# uC_input.net
KiCad netlist of a schematic drawn in Altium Designer
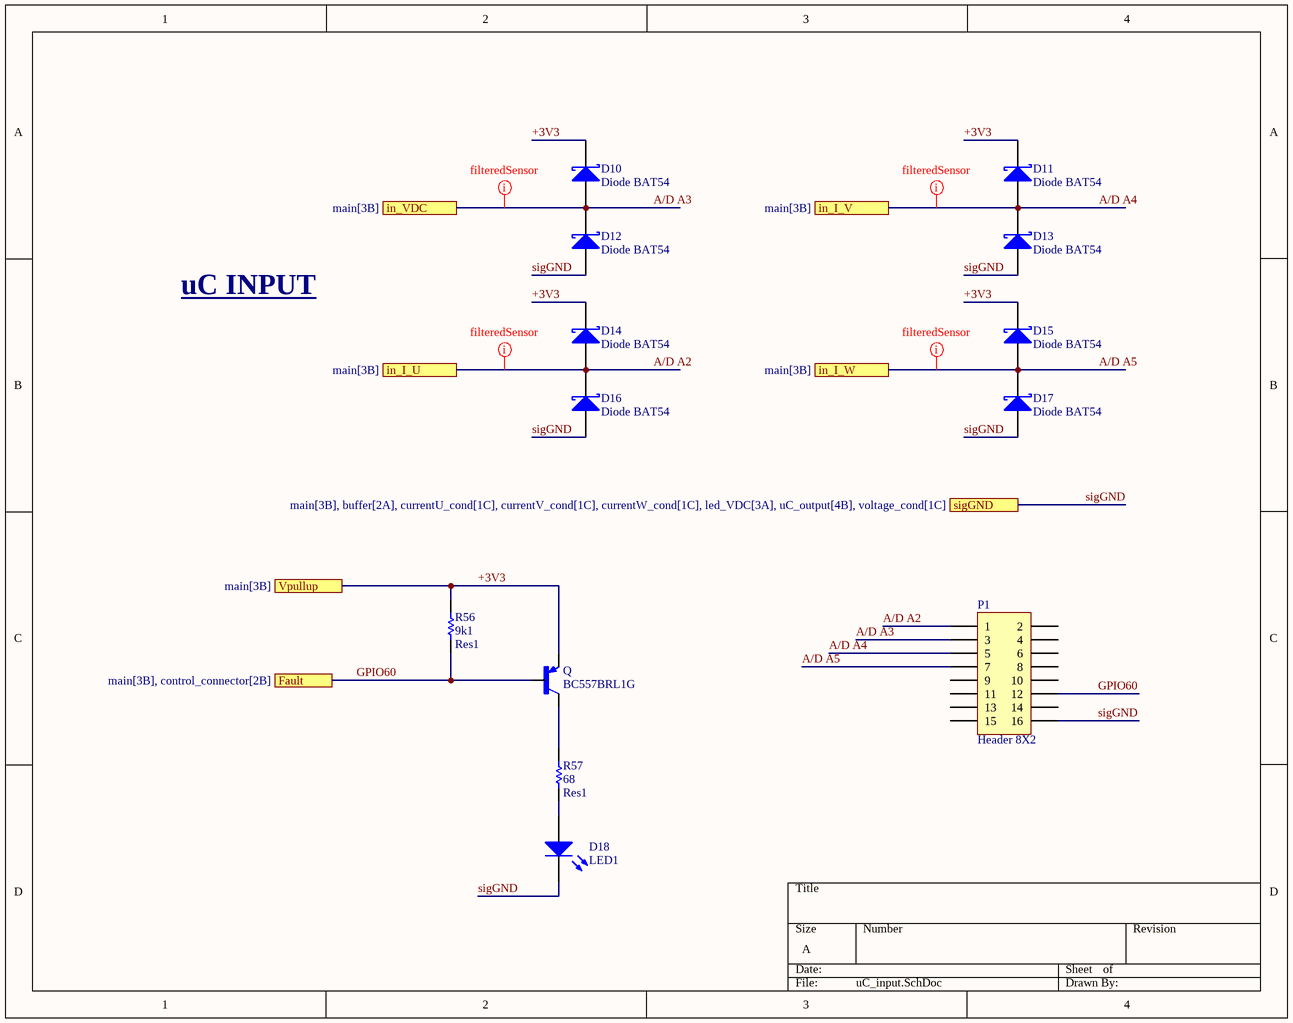
[diagram p0: uC_input.SchDoc]

(export (version "E")
  (design (tool "Eeschema 10.0.6"))
  (components
    (comp (ref "D10")
      (value "Diode BAT54")
      (footprint "DO-41_mod")
      (description "Schottky Rectifier")
      (fields (field (name "PUBLISHER") "Altium Limited"))
      (libsource (lib "LABSTEPS_Project") (part "Diode 11DQ03"))
    )
    (comp (ref "D11")
      (value "Diode BAT54")
      (footprint "DO-41_mod")
      (description "Schottky Rectifier")
      (fields (field (name "PUBLISHER") "Altium Limited"))
      (libsource (lib "LABSTEPS_Project") (part "Diode 11DQ03"))
    )
    (comp (ref "D12")
      (value "Diode BAT54")
      (footprint "DO-41_mod")
      (description "Schottky Rectifier")
      (fields (field (name "PUBLISHER") "Altium Limited"))
      (libsource (lib "LABSTEPS_Project") (part "Diode 11DQ03"))
    )
    (comp (ref "D13")
      (value "Diode BAT54")
      (footprint "DO-41_mod")
      (description "Schottky Rectifier")
      (fields (field (name "PUBLISHER") "Altium Limited"))
      (libsource (lib "LABSTEPS_Project") (part "Diode 11DQ03"))
    )
    (comp (ref "D14")
      (value "Diode BAT54")
      (footprint "DO-41_mod")
      (description "Schottky Rectifier")
      (fields (field (name "PUBLISHER") "Altium Limited"))
      (libsource (lib "LABSTEPS_Project") (part "Diode 11DQ03"))
    )
    (comp (ref "D15")
      (value "Diode BAT54")
      (footprint "DO-41_mod")
      (description "Schottky Rectifier")
      (fields (field (name "PUBLISHER") "Altium Limited"))
      (libsource (lib "LABSTEPS_Project") (part "Diode 11DQ03"))
    )
    (comp (ref "D16")
      (value "Diode BAT54")
      (footprint "DO-41_mod")
      (description "Schottky Rectifier")
      (fields (field (name "PUBLISHER") "Altium Limited"))
      (libsource (lib "LABSTEPS_Project") (part "Diode 11DQ03"))
    )
    (comp (ref "D17")
      (value "Diode BAT54")
      (footprint "DO-41_mod")
      (description "Schottky Rectifier")
      (fields (field (name "PUBLISHER") "Altium Limited"))
      (libsource (lib "LABSTEPS_Project") (part "Diode 11DQ03"))
    )
    (comp (ref "D18")
      (value "LED1")
      (footprint "PIN2_mod")
      (description "Typical RED GaAs LED")
      (fields (field (name "PUBLISHER") "Altium Limited"))
      (libsource (lib "moded_symbol") (part "LED1"))
    )
    (comp (ref "P1")
      (value "Header 8X2")
      (footprint "HDR2X8_mod")
      (description "Header, 8-Pin, Dual row")
      (fields (field (name "PUBLISHER") "Altium Limited"))
      (libsource (lib "LABSTEPS_Project") (part "Header 8X2"))
    )
    (comp (ref "Q")
      (value "BC557BRL1G")
      (footprint "TO92260P520H933-3_mod")
      (description "Bipolar (BJT) Transistor PNP 45V 100mA 320MHz 625mW Through Hole TO-92-3")
      (fields
        (field (name "MF") "ON Semiconductor")
        (field (name "BUYPART") "https://www.snapeda.com/parts/BC557BRL1G/ON%20Semiconductor/view-part/3219064/?ref=eda")
      )
      (libsource (lib "BC557") (part "BC557BRL1G"))
    )
    (comp (ref "R56")
      (value "Res1")
      (footprint "AXIAL-0.3_mod")
      (description "Resistor")
      (fields (field (name "ALTIUM_VALUE") "9k1") (field (name "PUBLISHER") "Altium Limited"))
      (libsource (lib "LABSTEPS_Project") (part "Res1"))
    )
    (comp (ref "R57")
      (value "Res1")
      (footprint "AXIAL-0.3_mod")
      (description "Resistor")
      (fields (field (name "ALTIUM_VALUE") "68") (field (name "PUBLISHER") "Altium Limited"))
      (libsource (lib "LABSTEPS_Project") (part "Res1"))
    )
  )
  (nets
    (net (code "1") (name "/+3V3") (class "Default")
      (node (ref "D10") (pin "2") (pinfunction "K_2") (pintype "passive"))
      (node (ref "D11") (pin "2") (pinfunction "K_2") (pintype "passive"))
      (node (ref "D14") (pin "2") (pinfunction "K_2") (pintype "passive"))
      (node (ref "D15") (pin "2") (pinfunction "K_2") (pintype "passive"))
      (node (ref "Q") (pin "3") (pinfunction "E_3") (pintype "passive"))
      (node (ref "R56") (pin "1") (pinfunction "1_1") (pintype "passive"))
    )
    (net (code "2") (name "/A{slash}D A2") (class "Default")
      (node (ref "D14") (pin "1") (pinfunction "A_1") (pintype "passive"))
      (node (ref "D16") (pin "2") (pinfunction "K_2") (pintype "passive"))
      (node (ref "P1") (pin "1") (pinfunction "1_1") (pintype "passive"))
    )
    (net (code "3") (name "/A{slash}D A3") (class "Default")
      (node (ref "D10") (pin "1") (pinfunction "A_1") (pintype "passive"))
      (node (ref "D12") (pin "2") (pinfunction "K_2") (pintype "passive"))
      (node (ref "P1") (pin "3") (pinfunction "3_3") (pintype "passive"))
    )
    (net (code "4") (name "/A{slash}D A4") (class "Default")
      (node (ref "D11") (pin "1") (pinfunction "A_1") (pintype "passive"))
      (node (ref "D13") (pin "2") (pinfunction "K_2") (pintype "passive"))
      (node (ref "P1") (pin "5") (pinfunction "5_5") (pintype "passive"))
    )
    (net (code "5") (name "/A{slash}D A5") (class "Default")
      (node (ref "D15") (pin "1") (pinfunction "A_1") (pintype "passive"))
      (node (ref "D17") (pin "2") (pinfunction "K_2") (pintype "passive"))
      (node (ref "P1") (pin "7") (pinfunction "7_7") (pintype "passive"))
    )
    (net (code "6") (name "/GPIO60") (class "Default")
      (node (ref "P1") (pin "12") (pinfunction "12_12") (pintype "passive"))
      (node (ref "Q") (pin "2") (pinfunction "B_2") (pintype "passive"))
      (node (ref "R56") (pin "2") (pinfunction "2_2") (pintype "passive"))
    )
    (net (code "7") (name "/sigGND") (class "Default")
      (node (ref "D12") (pin "1") (pinfunction "A_1") (pintype "passive"))
      (node (ref "D13") (pin "1") (pinfunction "A_1") (pintype "passive"))
      (node (ref "D16") (pin "1") (pinfunction "A_1") (pintype "passive"))
      (node (ref "D17") (pin "1") (pinfunction "A_1") (pintype "passive"))
      (node (ref "D18") (pin "2") (pinfunction "K_2") (pintype "passive"))
      (node (ref "P1") (pin "16") (pinfunction "16_16") (pintype "passive"))
    )
    (net (code "8") (name "Net-(D18-A)") (class "Default")
      (node (ref "D18") (pin "1") (pinfunction "A_1") (pintype "passive"))
      (node (ref "R57") (pin "2") (pinfunction "2_2") (pintype "passive"))
    )
    (net (code "9") (name "Net-(Q-C)") (class "Default")
      (node (ref "Q") (pin "1") (pinfunction "C_1") (pintype "passive"))
      (node (ref "R57") (pin "1") (pinfunction "1_1") (pintype "passive"))
    )
    (net (code "10") (name "unconnected-(P1-Pad2)") (class "Default")
      (node (ref "P1") (pin "2") (pinfunction "2_2") (pintype "passive"))
    )
    (net (code "11") (name "unconnected-(P1-Pad4)") (class "Default")
      (node (ref "P1") (pin "4") (pinfunction "4_4") (pintype "passive"))
    )
    (net (code "12") (name "unconnected-(P1-Pad6)") (class "Default")
      (node (ref "P1") (pin "6") (pinfunction "6_6") (pintype "passive"))
    )
    (net (code "13") (name "unconnected-(P1-Pad8)") (class "Default")
      (node (ref "P1") (pin "8") (pinfunction "8_8") (pintype "passive"))
    )
    (net (code "14") (name "unconnected-(P1-Pad9)") (class "Default")
      (node (ref "P1") (pin "9") (pinfunction "9_9") (pintype "passive"))
    )
    (net (code "15") (name "unconnected-(P1-Pad10)") (class "Default")
      (node (ref "P1") (pin "10") (pinfunction "10_10") (pintype "passive"))
    )
    (net (code "16") (name "unconnected-(P1-Pad11)") (class "Default")
      (node (ref "P1") (pin "11") (pinfunction "11_11") (pintype "passive"))
    )
    (net (code "17") (name "unconnected-(P1-Pad13)") (class "Default")
      (node (ref "P1") (pin "13") (pinfunction "13_13") (pintype "passive"))
    )
    (net (code "18") (name "unconnected-(P1-Pad14)") (class "Default")
      (node (ref "P1") (pin "14") (pinfunction "14_14") (pintype "passive"))
    )
    (net (code "19") (name "unconnected-(P1-Pad15)") (class "Default")
      (node (ref "P1") (pin "15") (pinfunction "15_15") (pintype "passive"))
    )
  )
)
